# CorroSenseBoard_V4_DaugtherBoard.net
KiCad netlist of a schematic drawn in Altium Designer
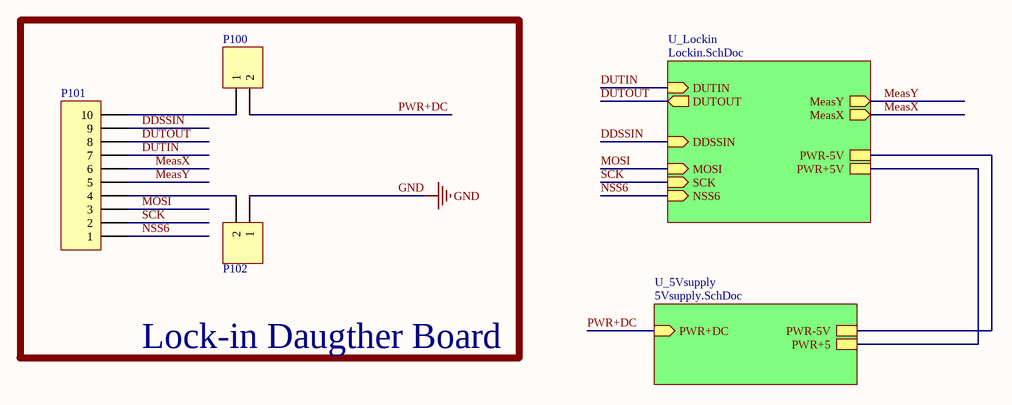
[diagram p0: CorroSenseBoard_V4_DaugtherBoard.SchDoc]

(export (version "E")
  (design (tool "Eeschema 10.0.6"))
  (components
    (comp (ref "P100")
      (value "Header, 2-Pin")
      (footprint "HDR1X2")
      (fields
        (field (name "MANUFACTURER") "Wurth Elektronik")
        (field (name "MPN") "61300211121")
        (field (name "PUBLISHER") "Altium Limited")
      )
      (libsource (lib "Miscellaneous Connectors") (part "Header 2"))
    )
    (comp (ref "P101")
      (value "Header, 10-Pin")
      (footprint "HDR1X10")
      (fields
        (field (name "MANUFACTURER") "Wurth Elektronik")
        (field (name "MPN") "61301011121")
        (field (name "PUBLISHER") "Altium Limited")
      )
      (libsource (lib "Miscellaneous Connectors") (part "Header 10"))
    )
    (comp (ref "P102")
      (value "Header, 2-Pin")
      (footprint "HDR1X2")
      (fields
        (field (name "MANUFACTURER") "Wurth Elektronik")
        (field (name "MPN") "61300211121")
        (field (name "PUBLISHER") "Altium Limited")
      )
      (libsource (lib "") (part "Header 2_1"))
    )
  )
  (nets
    (net (code "1") (name "/DDSSIN") (class "Default")
      (node (ref "P101") (pin "9") (pinfunction "9_9") (pintype "passive"))
    )
    (net (code "2") (name "/DUTIN") (class "Default")
      (node (ref "P101") (pin "7") (pinfunction "7_7") (pintype "passive"))
    )
    (net (code "3") (name "/DUTOUT") (class "Default")
      (node (ref "P101") (pin "8") (pinfunction "8_8") (pintype "passive"))
    )
    (net (code "4") (name "/MOSI") (class "Default")
      (node (ref "P101") (pin "3") (pinfunction "3_3") (pintype "passive"))
    )
    (net (code "5") (name "/MeasX") (class "Default")
      (node (ref "P101") (pin "6") (pinfunction "6_6") (pintype "passive"))
    )
    (net (code "6") (name "/MeasY") (class "Default")
      (node (ref "P101") (pin "5") (pinfunction "5_5") (pintype "passive"))
    )
    (net (code "7") (name "/NSS6") (class "Default")
      (node (ref "P101") (pin "1") (pinfunction "1_1") (pintype "passive"))
    )
    (net (code "9") (name "/PWR+DC") (class "Default")
      (node (ref "P100") (pin "2") (pinfunction "2_2") (pintype "passive"))
    )
    (net (code "11") (name "/SCK") (class "Default")
      (node (ref "P101") (pin "2") (pinfunction "2_2") (pintype "passive"))
    )
    (net (code "12") (name "GND") (class "Default")
      (node (ref "P102") (pin "1") (pinfunction "1_1") (pintype "passive"))
    )
    (net (code "13") (name "Net-(P100-Pad1)") (class "Default")
      (node (ref "P100") (pin "1") (pinfunction "1_1") (pintype "passive"))
      (node (ref "P101") (pin "10") (pinfunction "10_10") (pintype "passive"))
    )
    (net (code "14") (name "Net-(P101-Pad4)") (class "Default")
      (node (ref "P101") (pin "4") (pinfunction "4_4") (pintype "passive"))
      (node (ref "P102") (pin "2") (pinfunction "2_2") (pintype "passive"))
    )
  )
)
